# SoilSensor.net
KiCad netlist of a schematic drawn in EAGLE
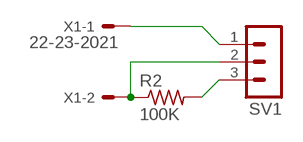
[diagram p0: schematic, sheet 1]

(export (version "E")
  (design (tool "Eeschema 10.0.6"))
  (components
    (comp (ref "R2")
      (value "100K")
      (footprint "eagle-import:0411_15")
      (libsource (lib "eagle-import") (part "R-US_0411/15"))
    )
    (comp (ref "SV1")
      (value "MA03-1")
      (footprint "eagle-import:MA03-1")
      (libsource (lib "eagle-import") (part "MA03-1"))
    )
    (comp (ref "X1")
      (value "22-23-2021")
      (footprint "eagle-import:22-23-2021")
      (fields (field (name "MF") "MOLEX"))
      (libsource (lib "eagle-import") (part "22-23-2021"))
    )
  )
  (nets
    (net (code "1") (name "Net-(R2-Pad2)") (class "Default")
      (node (ref "R2") (pin "2") (pinfunction "2_2") (pintype "passive"))
      (node (ref "SV1") (pin "3") (pinfunction "3_3") (pintype "passive"))
    )
    (net (code "2") (name "Net-(X1A-S)") (class "Default")
      (node (ref "SV1") (pin "1") (pinfunction "1_1") (pintype "passive"))
      (node (ref "X1") (pin "1") (pinfunction "S_1") (pintype "passive"))
    )
    (net (code "3") (name "Net-(X1B-S)") (class "Default")
      (node (ref "R2") (pin "1") (pinfunction "1_1") (pintype "passive"))
      (node (ref "SV1") (pin "2") (pinfunction "2_2") (pintype "passive"))
      (node (ref "X1") (pin "2") (pinfunction "S_2") (pintype "passive"))
    )
  )
)
